# BatteryMonitor_ADS1115.net
KiCad netlist of a schematic drawn in EAGLE
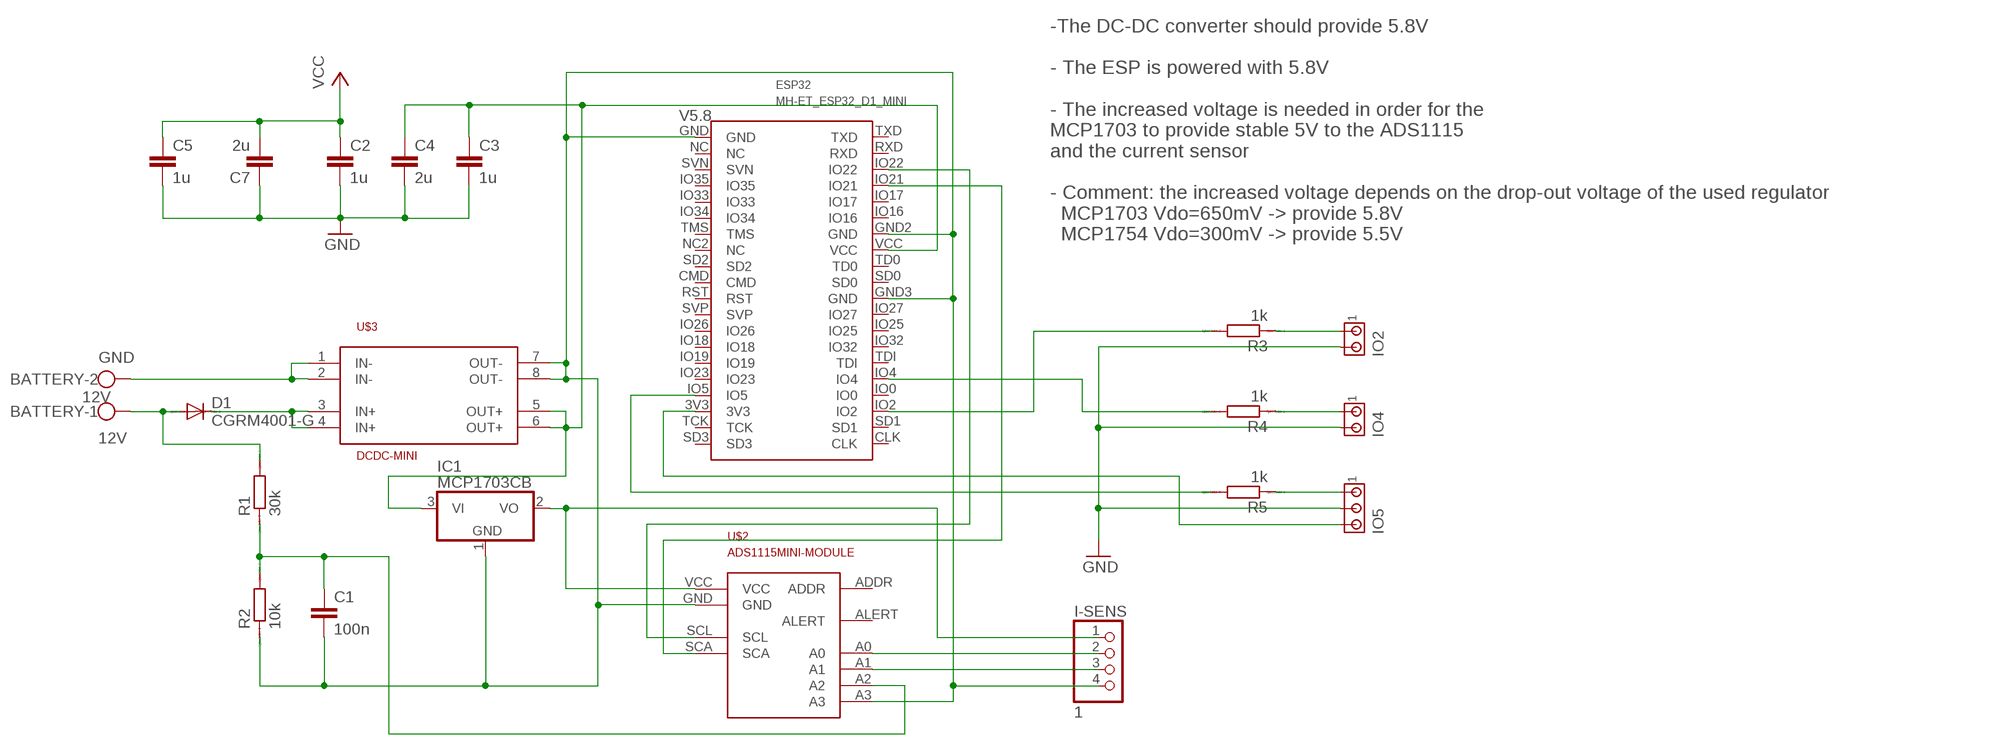
[diagram p0: schematic, sheet 1]

(export (version "E")
  (design (tool "Eeschema 10.0.6"))
  (components
    (comp (ref "BATTERY")
      (value "12V")
      (footprint "eagle-import:W237-102")
      (fields (field (name "MPN") "237-102") (field (name "VIN") "12V"))
      (libsource (lib "eagle-import") (part "W237-102"))
    )
    (comp (ref "C1")
      (value "100n")
      (footprint "eagle-import:C1206")
      (libsource (lib "eagle-import") (part "C-EUC1206"))
    )
    (comp (ref "C2")
      (value "1u")
      (footprint "eagle-import:C1206")
      (libsource (lib "eagle-import") (part "C-EUC1206"))
    )
    (comp (ref "C3")
      (value "1u")
      (footprint "eagle-import:C1206")
      (libsource (lib "eagle-import") (part "C-EUC1206"))
    )
    (comp (ref "C4")
      (value "2u")
      (footprint "eagle-import:C1206")
      (libsource (lib "eagle-import") (part "C-EUC1206"))
    )
    (comp (ref "C5")
      (value "1u")
      (footprint "eagle-import:C1206")
      (libsource (lib "eagle-import") (part "C-EUC1206"))
    )
    (comp (ref "C7")
      (value "2u")
      (footprint "eagle-import:C1206")
      (libsource (lib "eagle-import") (part "rcl_334_C-EUC1206"))
    )
    (comp (ref "D1")
      (value "CGRM4001-G")
      (footprint "eagle-import:SOD-123_MINI-SMA")
      (libsource (lib "eagle-import") (part "CGRM400-G1"))
    )
    (comp (ref "ESP32")
      (value "MH-ET_ESP32_D1_MINI")
      (footprint "eagle-import:MH-ET_ESP32_D1_MINI")
      (libsource (lib "eagle-import") (part "MH-ET_ESP32_D1_MINI"))
    )
    (comp (ref "I-SENS")
      (value "1")
      (footprint "eagle-import:1X04_90")
      (libsource (lib "eagle-import") (part "PINHD-1X4/90"))
    )
    (comp (ref "IC1")
      (value "MCP1703CB")
      (footprint "eagle-import:SOT23")
      (libsource (lib "eagle-import") (part "MCP1703CB"))
    )
    (comp (ref "IO2")
      (value "MTA02-100")
      (footprint "eagle-import:10X02MTA")
      (libsource (lib "eagle-import") (part "MTA02-100"))
    )
    (comp (ref "IO4")
      (value "MTA02-100")
      (footprint "eagle-import:10X02MTA")
      (libsource (lib "eagle-import") (part "MTA02-100"))
    )
    (comp (ref "IO5")
      (value "MTA03-100")
      (footprint "eagle-import:10X03MTA")
      (libsource (lib "eagle-import") (part "MTA03-100"))
    )
    (comp (ref "R1")
      (value "30k")
      (footprint "eagle-import:R1206")
      (libsource (lib "eagle-import") (part "RR1206"))
    )
    (comp (ref "R2")
      (value "10k")
      (footprint "eagle-import:R1206")
      (libsource (lib "eagle-import") (part "RR1206"))
    )
    (comp (ref "R3")
      (value "1k")
      (footprint "eagle-import:R1206")
      (libsource (lib "eagle-import") (part "RR1206"))
    )
    (comp (ref "R4")
      (value "1k")
      (footprint "eagle-import:R1206")
      (libsource (lib "eagle-import") (part "RR1206"))
    )
    (comp (ref "R5")
      (value "1k")
      (footprint "eagle-import:R1206")
      (libsource (lib "eagle-import") (part "RR1206"))
    )
    (comp (ref "U$2")
      (value "ADS1115MINI-MODULE")
      (footprint "eagle-import:ADS1115")
      (libsource (lib "eagle-import") (part "ADS1115MINI-MODULE"))
    )
    (comp (ref "U$3")
      (value "DCDC-MINI")
      (footprint "eagle-import:DCDC-MINI")
      (libsource (lib "eagle-import") (part "DCDC-MINI"))
    )
  )
  (nets
    (net (code "1") (name "/V5.8") (class "Default")
      (node (ref "C3") (pin "1") (pinfunction "1_1") (pintype "passive"))
      (node (ref "C4") (pin "1") (pinfunction "1_1") (pintype "passive"))
      (node (ref "ESP32") (pin "VCC") (pinfunction "VCC_VCC") (pintype "bidirectional"))
      (node (ref "IC1") (pin "3") (pinfunction "VI_3") (pintype "input"))
      (node (ref "U$3") (pin "5") (pinfunction "OUT+_5") (pintype "power_in"))
      (node (ref "U$3") (pin "6") (pinfunction "OUT+_6") (pintype "power_in"))
    )
    (net (code "2") (name "GND") (class "Default")
      (node (ref "BATTERY") (pin "2") (pinfunction "KL_2") (pintype "passive"))
      (node (ref "C1") (pin "2") (pinfunction "2_2") (pintype "passive"))
      (node (ref "C2") (pin "2") (pinfunction "2_2") (pintype "passive"))
      (node (ref "C3") (pin "2") (pinfunction "2_2") (pintype "passive"))
      (node (ref "C4") (pin "2") (pinfunction "2_2") (pintype "passive"))
      (node (ref "C5") (pin "2") (pinfunction "2_2") (pintype "passive"))
      (node (ref "C7") (pin "1") (pinfunction "1_1") (pintype "passive"))
      (node (ref "ESP32") (pin "GND") (pinfunction "GND_GND") (pintype "bidirectional"))
      (node (ref "ESP32") (pin "GND2") (pinfunction "GND_GND2") (pintype "bidirectional"))
      (node (ref "ESP32") (pin "GND3") (pinfunction "GND_GND3") (pintype "bidirectional"))
      (node (ref "I-SENS") (pin "4") (pinfunction "4_4") (pintype "passive"))
      (node (ref "IC1") (pin "1") (pinfunction "GND_1") (pintype "passive"))
      (node (ref "IO2") (pin "2") (pinfunction "2_2") (pintype "passive"))
      (node (ref "IO4") (pin "2") (pinfunction "2_2") (pintype "passive"))
      (node (ref "IO5") (pin "2") (pinfunction "2_2") (pintype "passive"))
      (node (ref "R2") (pin "1") (pinfunction "1_1") (pintype "passive"))
      (node (ref "U$2") (pin "A3") (pinfunction "A3_A3") (pintype "bidirectional"))
      (node (ref "U$2") (pin "GND") (pinfunction "GND_GND") (pintype "bidirectional"))
      (node (ref "U$3") (pin "1") (pinfunction "IN-_1") (pintype "power_in"))
      (node (ref "U$3") (pin "2") (pinfunction "IN-_2") (pintype "power_in"))
      (node (ref "U$3") (pin "7") (pinfunction "OUT-_7") (pintype "power_in"))
      (node (ref "U$3") (pin "8") (pinfunction "OUT-_8") (pintype "power_in"))
    )
    (net (code "3") (name "Net-(BATTERYA-KL)") (class "Default")
      (node (ref "BATTERY") (pin "1") (pinfunction "KL_1") (pintype "passive"))
      (node (ref "D1") (pin "A") (pinfunction "A_A") (pintype "passive"))
      (node (ref "R1") (pin "2") (pinfunction "2_2") (pintype "passive"))
    )
    (net (code "4") (name "Net-(C1-Pad1)") (class "Default")
      (node (ref "C1") (pin "1") (pinfunction "1_1") (pintype "passive"))
      (node (ref "R1") (pin "1") (pinfunction "1_1") (pintype "passive"))
      (node (ref "R2") (pin "2") (pinfunction "2_2") (pintype "passive"))
      (node (ref "U$2") (pin "A2") (pinfunction "A2_A2") (pintype "bidirectional"))
    )
    (net (code "5") (name "Net-(D1-PadC)") (class "Default")
      (node (ref "D1") (pin "C") (pinfunction "C_C") (pintype "passive"))
      (node (ref "U$3") (pin "3") (pinfunction "IN+_3") (pintype "power_in"))
      (node (ref "U$3") (pin "4") (pinfunction "IN+_4") (pintype "power_in"))
    )
    (net (code "6") (name "Net-(ESP32-Pad3V3)") (class "Default")
      (node (ref "ESP32") (pin "3V3") (pinfunction "3V3_3V3") (pintype "bidirectional"))
      (node (ref "IO5") (pin "3") (pinfunction "3_3") (pintype "passive"))
    )
    (net (code "7") (name "Net-(ESP32-PadIO2)") (class "Default")
      (node (ref "ESP32") (pin "IO2") (pinfunction "IO2_IO2") (pintype "bidirectional"))
      (node (ref "R3") (pin "2") (pinfunction "2_2") (pintype "passive"))
    )
    (net (code "8") (name "Net-(ESP32-PadIO4)") (class "Default")
      (node (ref "ESP32") (pin "IO4") (pinfunction "IO4_IO4") (pintype "bidirectional"))
      (node (ref "R4") (pin "2") (pinfunction "2_2") (pintype "passive"))
    )
    (net (code "9") (name "Net-(ESP32-PadIO5)") (class "Default")
      (node (ref "ESP32") (pin "IO5") (pinfunction "IO5_IO5") (pintype "bidirectional"))
      (node (ref "R5") (pin "2") (pinfunction "2_2") (pintype "passive"))
    )
    (net (code "10") (name "Net-(ESP32-PadIO21)") (class "Default")
      (node (ref "ESP32") (pin "IO21") (pinfunction "IO21_IO21") (pintype "bidirectional"))
      (node (ref "U$2") (pin "SCA") (pinfunction "SCA_SCA") (pintype "bidirectional"))
    )
    (net (code "11") (name "Net-(ESP32-PadIO22)") (class "Default")
      (node (ref "ESP32") (pin "IO22") (pinfunction "IO22_IO22") (pintype "bidirectional"))
      (node (ref "U$2") (pin "SCL") (pinfunction "SCL_SCL") (pintype "bidirectional"))
    )
    (net (code "12") (name "Net-(I-SENS-Pad2)") (class "Default")
      (node (ref "I-SENS") (pin "2") (pinfunction "2_2") (pintype "passive"))
      (node (ref "U$2") (pin "A0") (pinfunction "A0_A0") (pintype "bidirectional"))
    )
    (net (code "13") (name "Net-(I-SENS-Pad3)") (class "Default")
      (node (ref "I-SENS") (pin "3") (pinfunction "3_3") (pintype "passive"))
      (node (ref "U$2") (pin "A1") (pinfunction "A1_A1") (pintype "bidirectional"))
    )
    (net (code "14") (name "Net-(IO2-Pad1)") (class "Default")
      (node (ref "IO2") (pin "1") (pinfunction "1_1") (pintype "passive"))
      (node (ref "R3") (pin "1") (pinfunction "1_1") (pintype "passive"))
    )
    (net (code "15") (name "Net-(IO4-Pad1)") (class "Default")
      (node (ref "IO4") (pin "1") (pinfunction "1_1") (pintype "passive"))
      (node (ref "R4") (pin "1") (pinfunction "1_1") (pintype "passive"))
    )
    (net (code "16") (name "Net-(IO5-Pad1)") (class "Default")
      (node (ref "IO5") (pin "1") (pinfunction "1_1") (pintype "passive"))
      (node (ref "R5") (pin "1") (pinfunction "1_1") (pintype "passive"))
    )
    (net (code "17") (name "VCC") (class "Default")
      (node (ref "C2") (pin "1") (pinfunction "1_1") (pintype "passive"))
      (node (ref "C5") (pin "1") (pinfunction "1_1") (pintype "passive"))
      (node (ref "C7") (pin "2") (pinfunction "2_2") (pintype "passive"))
      (node (ref "I-SENS") (pin "1") (pinfunction "1_1") (pintype "passive"))
      (node (ref "IC1") (pin "2") (pinfunction "VO_2") (pintype "passive"))
      (node (ref "U$2") (pin "VCC") (pinfunction "VCC_VCC") (pintype "bidirectional"))
    )
    (net (code "18") (name "unconnected-(ESP32-NC-PadNC2)") (class "Default")
      (node (ref "ESP32") (pin "NC2") (pinfunction "NC_NC2") (pintype "bidirectional"))
    )
    (net (code "19") (name "unconnected-(ESP32-PadCLK)") (class "Default")
      (node (ref "ESP32") (pin "CLK") (pinfunction "CLK_CLK") (pintype "bidirectional"))
    )
    (net (code "20") (name "unconnected-(ESP32-PadCMD)") (class "Default")
      (node (ref "ESP32") (pin "CMD") (pinfunction "CMD_CMD") (pintype "bidirectional"))
    )
    (net (code "21") (name "unconnected-(ESP32-PadIO0)") (class "Default")
      (node (ref "ESP32") (pin "IO0") (pinfunction "IO0_IO0") (pintype "bidirectional"))
    )
    (net (code "22") (name "unconnected-(ESP32-PadIO16)") (class "Default")
      (node (ref "ESP32") (pin "IO16") (pinfunction "IO16_IO16") (pintype "bidirectional"))
    )
    (net (code "23") (name "unconnected-(ESP32-PadIO17)") (class "Default")
      (node (ref "ESP32") (pin "IO17") (pinfunction "IO17_IO17") (pintype "bidirectional"))
    )
    (net (code "24") (name "unconnected-(ESP32-PadIO18)") (class "Default")
      (node (ref "ESP32") (pin "IO18") (pinfunction "IO18_IO18") (pintype "bidirectional"))
    )
    (net (code "25") (name "unconnected-(ESP32-PadIO19)") (class "Default")
      (node (ref "ESP32") (pin "IO19") (pinfunction "IO19_IO19") (pintype "bidirectional"))
    )
    (net (code "26") (name "unconnected-(ESP32-PadIO23)") (class "Default")
      (node (ref "ESP32") (pin "IO23") (pinfunction "IO23_IO23") (pintype "bidirectional"))
    )
    (net (code "27") (name "unconnected-(ESP32-PadIO25)") (class "Default")
      (node (ref "ESP32") (pin "IO25") (pinfunction "IO25_IO25") (pintype "bidirectional"))
    )
    (net (code "28") (name "unconnected-(ESP32-PadIO26)") (class "Default")
      (node (ref "ESP32") (pin "IO26") (pinfunction "IO26_IO26") (pintype "bidirectional"))
    )
    (net (code "29") (name "unconnected-(ESP32-PadIO27)") (class "Default")
      (node (ref "ESP32") (pin "IO27") (pinfunction "IO27_IO27") (pintype "bidirectional"))
    )
    (net (code "30") (name "unconnected-(ESP32-PadIO32)") (class "Default")
      (node (ref "ESP32") (pin "IO32") (pinfunction "IO32_IO32") (pintype "bidirectional"))
    )
    (net (code "31") (name "unconnected-(ESP32-PadIO33)") (class "Default")
      (node (ref "ESP32") (pin "IO33") (pinfunction "IO33_IO33") (pintype "bidirectional"))
    )
    (net (code "32") (name "unconnected-(ESP32-PadIO34)") (class "Default")
      (node (ref "ESP32") (pin "IO34") (pinfunction "IO34_IO34") (pintype "bidirectional"))
    )
    (net (code "33") (name "unconnected-(ESP32-PadIO35)") (class "Default")
      (node (ref "ESP32") (pin "IO35") (pinfunction "IO35_IO35") (pintype "bidirectional"))
    )
    (net (code "34") (name "unconnected-(ESP32-PadNC)") (class "Default")
      (node (ref "ESP32") (pin "NC") (pinfunction "NC_NC") (pintype "bidirectional"))
    )
    (net (code "35") (name "unconnected-(ESP32-PadRST)") (class "Default")
      (node (ref "ESP32") (pin "RST") (pinfunction "RST_RST") (pintype "bidirectional"))
    )
    (net (code "36") (name "unconnected-(ESP32-PadRXD)") (class "Default")
      (node (ref "ESP32") (pin "RXD") (pinfunction "RXD_RXD") (pintype "bidirectional"))
    )
    (net (code "37") (name "unconnected-(ESP32-PadSD0)") (class "Default")
      (node (ref "ESP32") (pin "SD0") (pinfunction "SD0_SD0") (pintype "bidirectional"))
    )
    (net (code "38") (name "unconnected-(ESP32-PadSD1)") (class "Default")
      (node (ref "ESP32") (pin "SD1") (pinfunction "SD1_SD1") (pintype "bidirectional"))
    )
    (net (code "39") (name "unconnected-(ESP32-PadSD2)") (class "Default")
      (node (ref "ESP32") (pin "SD2") (pinfunction "SD2_SD2") (pintype "bidirectional"))
    )
    (net (code "40") (name "unconnected-(ESP32-PadSD3)") (class "Default")
      (node (ref "ESP32") (pin "SD3") (pinfunction "SD3_SD3") (pintype "bidirectional"))
    )
    (net (code "41") (name "unconnected-(ESP32-PadSVN)") (class "Default")
      (node (ref "ESP32") (pin "SVN") (pinfunction "SVN_SVN") (pintype "bidirectional"))
    )
    (net (code "42") (name "unconnected-(ESP32-PadSVP)") (class "Default")
      (node (ref "ESP32") (pin "SVP") (pinfunction "SVP_SVP") (pintype "bidirectional"))
    )
    (net (code "43") (name "unconnected-(ESP32-PadTCK)") (class "Default")
      (node (ref "ESP32") (pin "TCK") (pinfunction "TCK_TCK") (pintype "bidirectional"))
    )
    (net (code "44") (name "unconnected-(ESP32-PadTD0)") (class "Default")
      (node (ref "ESP32") (pin "TD0") (pinfunction "TD0_TD0") (pintype "bidirectional"))
    )
    (net (code "45") (name "unconnected-(ESP32-PadTDI)") (class "Default")
      (node (ref "ESP32") (pin "TDI") (pinfunction "TDI_TDI") (pintype "bidirectional"))
    )
    (net (code "46") (name "unconnected-(ESP32-PadTMS)") (class "Default")
      (node (ref "ESP32") (pin "TMS") (pinfunction "TMS_TMS") (pintype "bidirectional"))
    )
    (net (code "47") (name "unconnected-(ESP32-PadTXD)") (class "Default")
      (node (ref "ESP32") (pin "TXD") (pinfunction "TXD_TXD") (pintype "bidirectional"))
    )
    (net (code "48") (name "unconnected-(U$2-PadADDR)") (class "Default")
      (node (ref "U$2") (pin "ADDR") (pinfunction "ADDR_ADDR") (pintype "bidirectional"))
    )
    (net (code "49") (name "unconnected-(U$2-PadALERT)") (class "Default")
      (node (ref "U$2") (pin "ALERT") (pinfunction "ALERT_ALERT") (pintype "bidirectional"))
    )
  )
)
